# twentyfour.net
KiCad netlist of a schematic drawn in Altium Designer
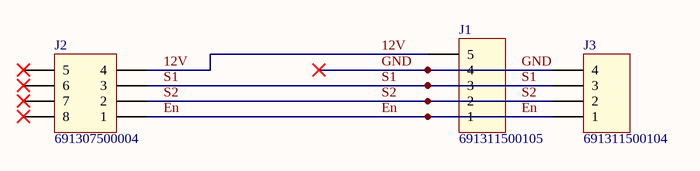
[diagram p0: twentyfour.SchDoc]

(export (version "E")
  (design (tool "Eeschema 10.0.6"))
  (components
    (comp (ref "J1")
      (value "691311500105")
      (footprint "691311500105")
      (description "WR-TBL Serie 311 - 5.08 mm Close Vertical PCB Header, 05p")
      (fields (field (name "PUBLISHER") "Wurth Elektronik"))
      (libsource (lib "ALTIUM-TBL_5_08_3075_REVERSED_GENDER_VERTICAL_PCB_HEADER_69130750000X-rev17a") (part "691311500105"))
    )
    (comp (ref "J2")
      (value "691307500004")
      (footprint "691307500004")
      (description "WR-TBL Serie 3075 - 5.08 mm Reversed Gender Vertical PCB Header, 04p")
      (fields (field (name "PUBLISHER") "Wurth Elektronik"))
      (libsource (lib "ALTIUM-TBL_5_08_3075_REVERSED_GENDER_VERTICAL_PCB_HEADER_69130750000X-rev17a") (part "691307500004"))
    )
    (comp (ref "J3")
      (value "691311500104")
      (footprint "691311500104")
      (description "WR-TBL Serie 311 - 5.08 mm Close Vertical PCB Header, 04p")
      (fields (field (name "PUBLISHER") "Wurth Elektronik"))
      (libsource (lib "ALTIUM-TBL_5_08_3075_REVERSED_GENDER_VERTICAL_PCB_HEADER_69130750000X-rev17a") (part "691311500104"))
    )
  )
  (nets
    (net (code "1") (name "/12V") (class "Default")
      (node (ref "J1") (pin "5") (pinfunction "5_5") (pintype "passive"))
      (node (ref "J2") (pin "4") (pinfunction "4_4") (pintype "passive"))
    )
    (net (code "2") (name "/En") (class "Default")
      (node (ref "J1") (pin "1") (pinfunction "1_1") (pintype "passive"))
      (node (ref "J2") (pin "1") (pinfunction "1_1") (pintype "passive"))
      (node (ref "J3") (pin "1") (pinfunction "1_1") (pintype "passive"))
    )
    (net (code "3") (name "/GND") (class "Default")
      (node (ref "J1") (pin "4") (pinfunction "4_4") (pintype "passive"))
      (node (ref "J3") (pin "4") (pinfunction "4_4") (pintype "passive"))
    )
    (net (code "4") (name "/S1") (class "Default")
      (node (ref "J1") (pin "3") (pinfunction "3_3") (pintype "passive"))
      (node (ref "J2") (pin "3") (pinfunction "3_3") (pintype "passive"))
      (node (ref "J3") (pin "3") (pinfunction "3_3") (pintype "passive"))
    )
    (net (code "5") (name "/S2") (class "Default")
      (node (ref "J1") (pin "2") (pinfunction "2_2") (pintype "passive"))
      (node (ref "J2") (pin "2") (pinfunction "2_2") (pintype "passive"))
      (node (ref "J3") (pin "2") (pinfunction "2_2") (pintype "passive"))
    )
    (net (code "6") (name "unconnected-(J2-Pad5)") (class "Default")
      (node (ref "J2") (pin "5") (pinfunction "5_5") (pintype "passive+no_connect"))
    )
    (net (code "7") (name "unconnected-(J2-Pad6)") (class "Default")
      (node (ref "J2") (pin "6") (pinfunction "6_6") (pintype "passive+no_connect"))
    )
    (net (code "8") (name "unconnected-(J2-Pad7)") (class "Default")
      (node (ref "J2") (pin "7") (pinfunction "7_7") (pintype "passive+no_connect"))
    )
    (net (code "9") (name "unconnected-(J2-Pad8)") (class "Default")
      (node (ref "J2") (pin "8") (pinfunction "8_8") (pintype "passive+no_connect"))
    )
  )
)
